# Spinn.net
KiCad netlist of a schematic drawn in Altium Designer
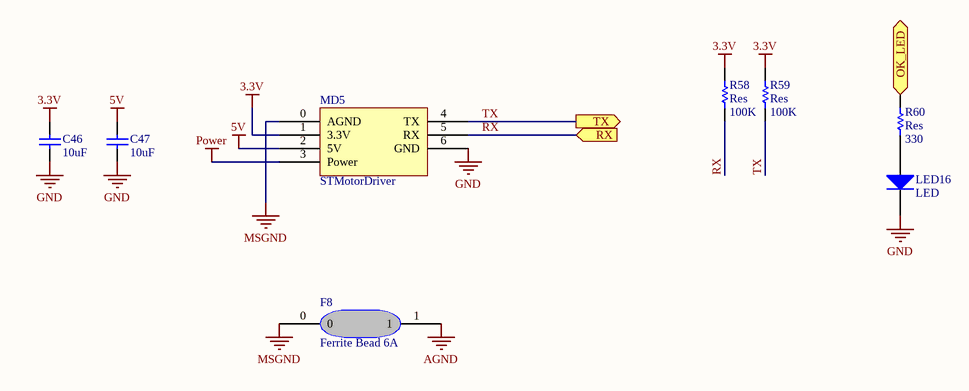
[diagram p0: Spinn.SchDoc]

(export (version "E")
  (design (tool "Eeschema 10.0.6"))
  (components
    (comp (ref "C46")
      (value "10uF")
      (footprint "2012[0805]")
      (description "Capacitor")
      (fields (field (name "Comment") "Cap_UP") (field (name "PUBLISHER") "Altium Limited"))
      (libsource (lib "KN2CLib") (part "Cap_UP"))
    )
    (comp (ref "C47")
      (value "10uF")
      (footprint "2012[0805]")
      (description "Capacitor")
      (fields (field (name "Comment") "Cap_UP") (field (name "PUBLISHER") "Altium Limited"))
      (libsource (lib "KN2CLib") (part "Cap_UP"))
    )
    (comp (ref "F8")
      (value "Ferrite Bead 6A")
      (footprint "f6A")
      (libsource (lib "Ferrite Bead") (part "F6A"))
    )
    (comp (ref "LED16")
      (value "LED")
      (footprint "2012[0805]")
      (description "1 Amp General Purpose Rectifier")
      (fields (field (name "PUBLISHER") "Altium Limited"))
      (libsource (lib "KN2CLib") (part "Diode"))
    )
    (comp (ref "MD5")
      (value "STMotorDriver")
      (footprint "MotorDriver")
      (libsource (lib "STMotorDriver") (part "STMotorDriver"))
    )
    (comp (ref "R58")
      (value "Res")
      (footprint "2012[0805]")
      (description "Semiconductor Resistor")
      (fields (field (name "ALTIUM_VALUE") "100K") (field (name "PUBLISHER") "Altium Limited"))
      (libsource (lib "KN2CLib") (part "Res"))
    )
    (comp (ref "R59")
      (value "Res")
      (footprint "2012[0805]")
      (description "Semiconductor Resistor")
      (fields (field (name "ALTIUM_VALUE") "100K") (field (name "PUBLISHER") "Altium Limited"))
      (libsource (lib "KN2CLib") (part "Res"))
    )
    (comp (ref "R60")
      (value "Res")
      (footprint "2012[0805]")
      (description "Semiconductor Resistor")
      (fields (field (name "ALTIUM_VALUE") "330") (field (name "PUBLISHER") "Altium Limited"))
      (libsource (lib "KN2CLib") (part "Res"))
    )
  )
  (nets
    (net (code "1") (name "/OK_LED") (class "Default")
      (node (ref "R60") (pin "1") (pinfunction "1_1") (pintype "passive"))
    )
    (net (code "2") (name "/RX") (class "Default")
      (node (ref "MD5") (pin "5") (pinfunction "RX_5") (pintype "passive"))
      (node (ref "R58") (pin "1") (pinfunction "1_1") (pintype "passive"))
    )
    (net (code "3") (name "/TX") (class "Default")
      (node (ref "MD5") (pin "4") (pinfunction "TX_4") (pintype "passive"))
      (node (ref "R59") (pin "1") (pinfunction "1_1") (pintype "passive"))
    )
    (net (code "4") (name "3.3V") (class "Default")
      (node (ref "C46") (pin "2") (pinfunction "2_2") (pintype "passive"))
      (node (ref "MD5") (pin "1") (pinfunction "3.3V_1") (pintype "passive"))
      (node (ref "R58") (pin "2") (pinfunction "2_2") (pintype "passive"))
      (node (ref "R59") (pin "2") (pinfunction "2_2") (pintype "passive"))
    )
    (net (code "5") (name "5V") (class "Default")
      (node (ref "C47") (pin "2") (pinfunction "2_2") (pintype "passive"))
      (node (ref "MD5") (pin "2") (pinfunction "5V_2") (pintype "passive"))
    )
    (net (code "6") (name "AGND") (class "Default")
      (node (ref "F8") (pin "1") (pinfunction "1_1") (pintype "passive"))
    )
    (net (code "7") (name "GND") (class "Default")
      (node (ref "C46") (pin "1") (pinfunction "1_1") (pintype "passive"))
      (node (ref "C47") (pin "1") (pinfunction "1_1") (pintype "passive"))
      (node (ref "LED16") (pin "2") (pinfunction "K_2") (pintype "passive"))
      (node (ref "MD5") (pin "6") (pinfunction "GND_6") (pintype "passive"))
    )
    (net (code "8") (name "MSGND") (class "Default")
      (node (ref "F8") (pin "0") (pinfunction "0_0") (pintype "passive"))
      (node (ref "MD5") (pin "0") (pinfunction "AGND_0") (pintype "passive"))
    )
    (net (code "9") (name "Net-(LED16-A)") (class "Default")
      (node (ref "LED16") (pin "1") (pinfunction "A_1") (pintype "passive"))
      (node (ref "R60") (pin "2") (pinfunction "2_2") (pintype "passive"))
    )
    (net (code "10") (name "Power") (class "Default")
      (node (ref "MD5") (pin "3") (pinfunction "Power_3") (pintype "passive"))
    )
  )
)
